# HABduino1_1.net
KiCad netlist of a schematic drawn in EAGLE
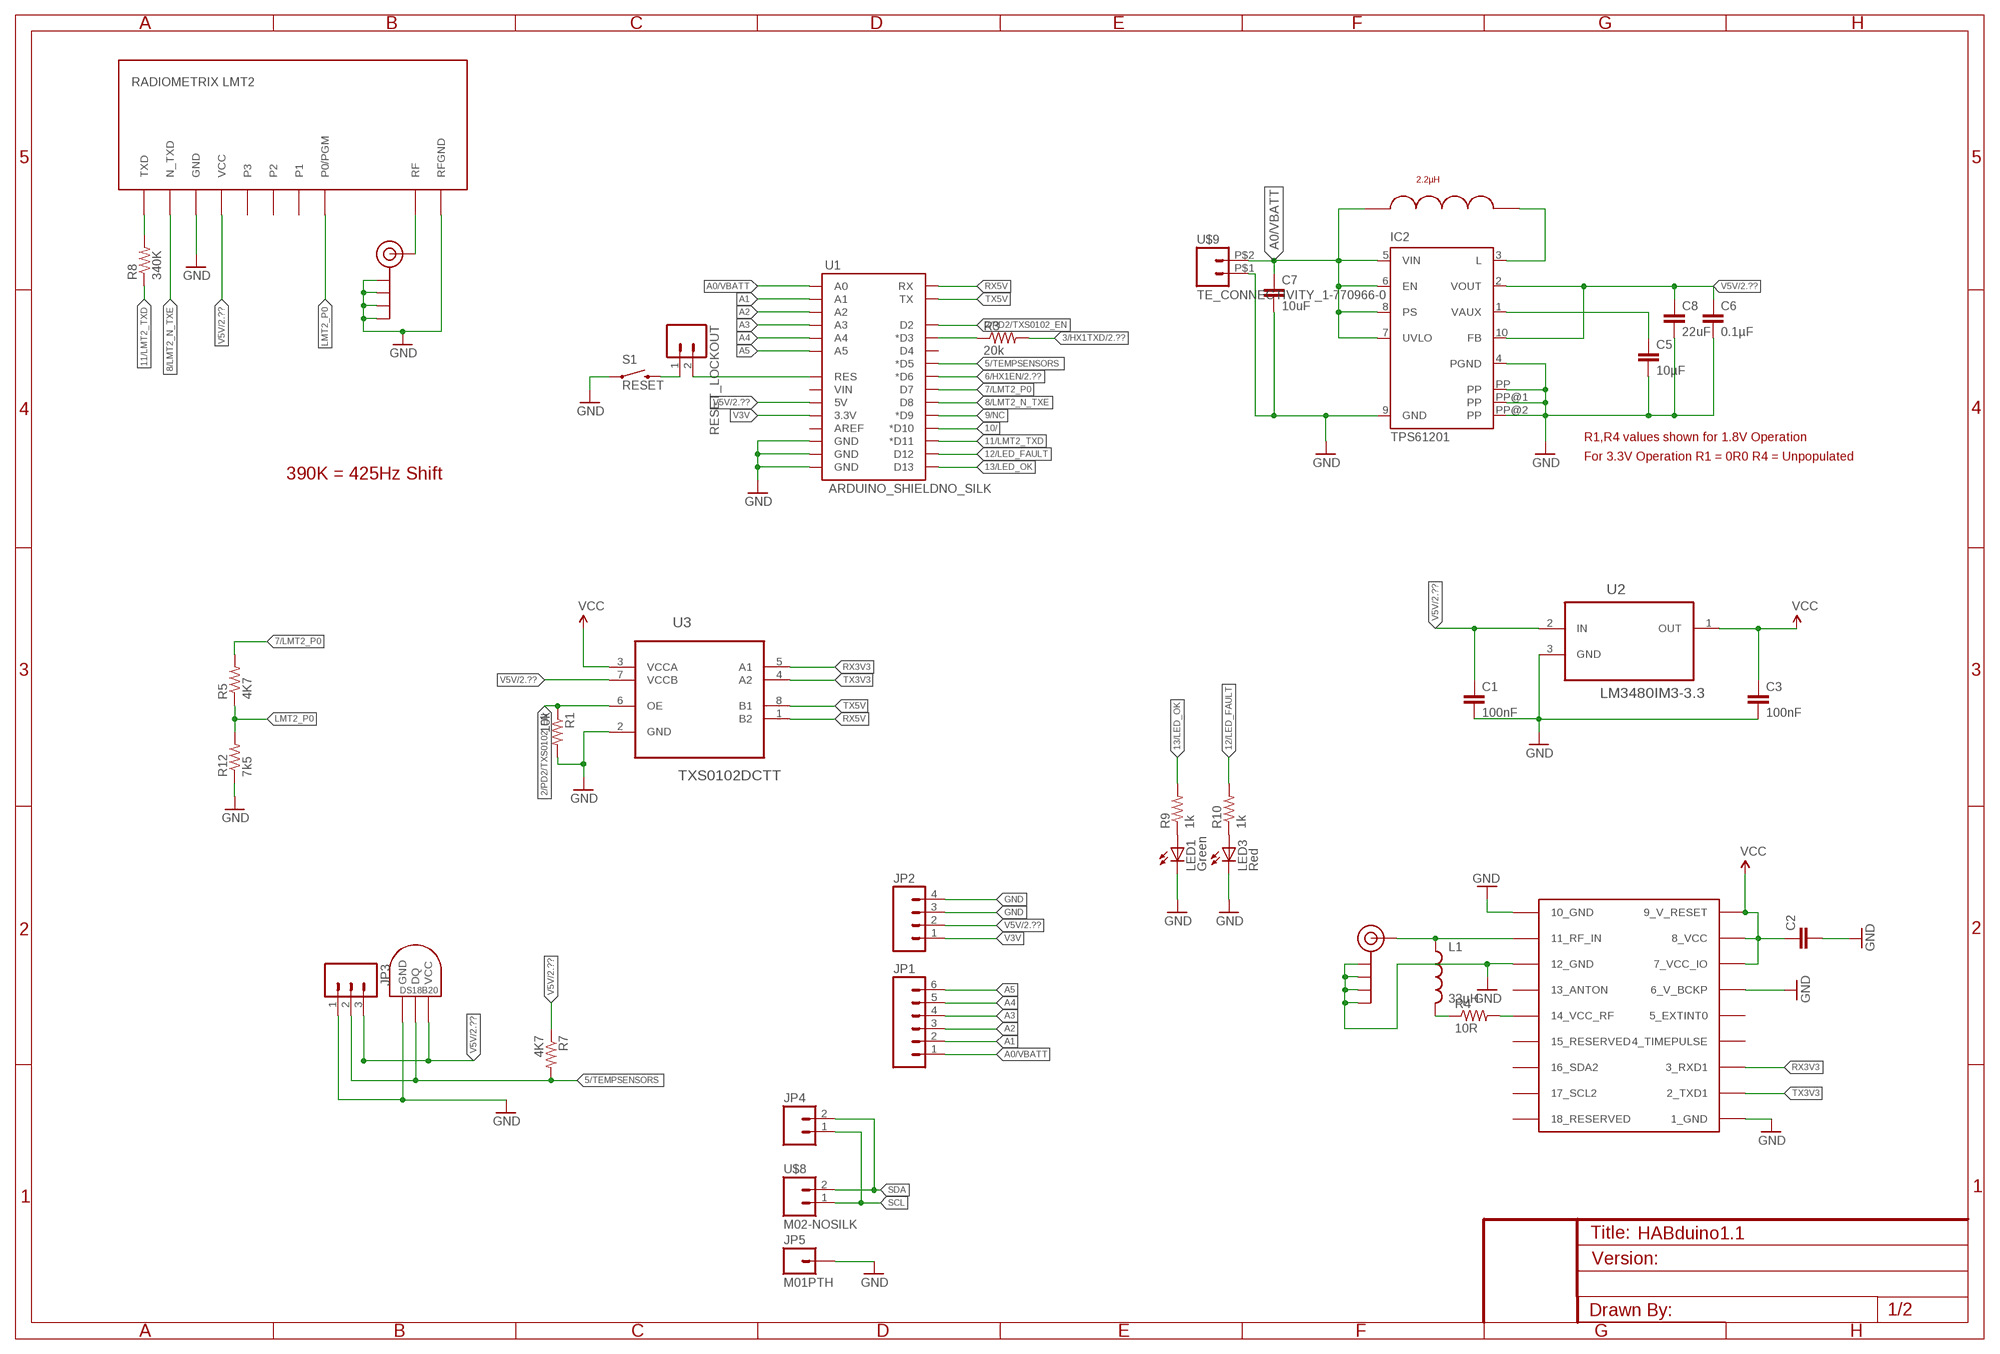
[diagram p0: schematic, sheet 1]
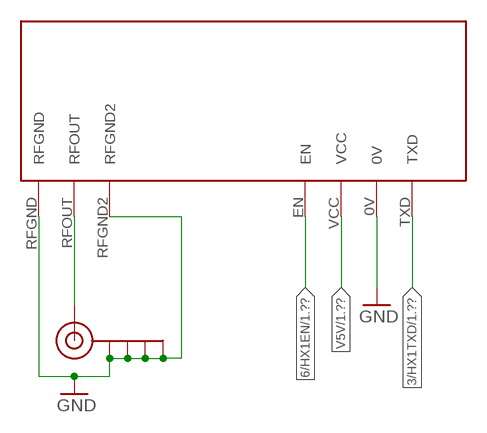
[diagram p1: schematic, sheet 2]

(export (version "E")
  (design (tool "Eeschema 10.0.6"))
  (components
    (comp (ref "C1")
      (value "100nF")
      (footprint "eagle-import:0603-CAP")
      (libsource (lib "eagle-import") (part "CAP0603-CAP"))
    )
    (comp (ref "C2")
      (value "CAP0603-CAP")
      (footprint "eagle-import:0603-CAP")
      (libsource (lib "eagle-import") (part "CAP0603-CAP"))
    )
    (comp (ref "C3")
      (value "100nF")
      (footprint "eagle-import:0603-CAP")
      (libsource (lib "eagle-import") (part "CAP0603-CAP"))
    )
    (comp (ref "C5")
      (value "10µF")
      (footprint "eagle-import:0603-CAP")
      (libsource (lib "eagle-import") (part "CAP0603-CAP"))
    )
    (comp (ref "C6")
      (value "0.1µF")
      (footprint "eagle-import:0603-CAP")
      (libsource (lib "eagle-import") (part "CAP0603-CAP"))
    )
    (comp (ref "C7")
      (value "10uF")
      (footprint "eagle-import:1206")
      (libsource (lib "eagle-import") (part "CAP1206"))
    )
    (comp (ref "C8")
      (value "22uF")
      (footprint "eagle-import:1206")
      (libsource (lib "eagle-import") (part "CAP1206"))
    )
    (comp (ref "IC2")
      (value "TPS61201")
      (footprint "eagle-import:S-PDSO-N10")
      (fields (field (name "MPN") "TPS61201DRCT"))
      (libsource (lib "eagle-import") (part "TPS61201"))
    )
    (comp (ref "J$1")
      (value "SMA_EDGE")
      (footprint "eagle-import:SMA-EDGE")
      (libsource (lib "eagle-import") (part "SMA_EDGE"))
    )
    (comp (ref "J$2")
      (value "SMA_EDGE")
      (footprint "eagle-import:SMA-EDGE")
      (libsource (lib "eagle-import") (part "SMA_EDGE"))
    )
    (comp (ref "JP1")
      (value "M06SIP")
      (footprint "eagle-import:1X06")
      (libsource (lib "eagle-import") (part "M06SIP"))
    )
    (comp (ref "JP2")
      (value "M04PTH")
      (footprint "eagle-import:1X04")
      (libsource (lib "eagle-import") (part "M04PTH"))
    )
    (comp (ref "JP3")
      (value "M03PTH")
      (footprint "eagle-import:1X03")
      (libsource (lib "eagle-import") (part "M03PTH"))
    )
    (comp (ref "JP4")
      (value "M02PTH")
      (footprint "eagle-import:1X02")
      (libsource (lib "eagle-import") (part "M02PTH"))
    )
    (comp (ref "JP5")
      (value "M01PTH")
      (footprint "eagle-import:1X01")
      (libsource (lib "eagle-import") (part "M01PTH"))
    )
    (comp (ref "L1")
      (value "33µH")
      (footprint "eagle-import:0603")
      (libsource (lib "eagle-import") (part "INDUCTOR0603"))
    )
    (comp (ref "LED1")
      (value "Green")
      (footprint "eagle-import:LED-0603")
      (libsource (lib "eagle-import") (part "LED0603"))
    )
    (comp (ref "LED3")
      (value "Red")
      (footprint "eagle-import:LED-0603")
      (libsource (lib "eagle-import") (part "LED0603"))
    )
    (comp (ref "R1")
      (value "10k")
      (footprint "eagle-import:0603-RES")
      (libsource (lib "eagle-import") (part "RESISTOR0603-RES"))
    )
    (comp (ref "R3")
      (value "20k")
      (footprint "eagle-import:0603-RES")
      (libsource (lib "eagle-import") (part "RESISTOR0603-RES"))
    )
    (comp (ref "R4")
      (value "10R")
      (footprint "eagle-import:0603-RES")
      (libsource (lib "eagle-import") (part "RESISTOR0603-RES"))
    )
    (comp (ref "R5")
      (value "4K7")
      (footprint "eagle-import:0603-RES")
      (libsource (lib "eagle-import") (part "RESISTOR0603-RES"))
    )
    (comp (ref "R7")
      (value "4K7")
      (footprint "eagle-import:0603-RES")
      (libsource (lib "eagle-import") (part "RESISTOR0603-RES"))
    )
    (comp (ref "R8")
      (value "340K")
      (footprint "eagle-import:0603-RES")
      (libsource (lib "eagle-import") (part "RESISTOR0603-RES"))
    )
    (comp (ref "R9")
      (value "1k")
      (footprint "eagle-import:0603-RES")
      (libsource (lib "eagle-import") (part "RESISTOR0603-RES"))
    )
    (comp (ref "R10")
      (value "1k")
      (footprint "eagle-import:0603-RES")
      (libsource (lib "eagle-import") (part "RESISTOR0603-RES"))
    )
    (comp (ref "R12")
      (value "7k5")
      (footprint "eagle-import:0603-RES")
      (libsource (lib "eagle-import") (part "RESISTOR0603-RES"))
    )
    (comp (ref "RESET_LOCKOUT")
      (value "M02PTH")
      (footprint "eagle-import:1X02")
      (libsource (lib "eagle-import") (part "M02PTH"))
    )
    (comp (ref "S1")
      (value "RESET")
      (footprint "eagle-import:TACTILE_SWITCH_TALL")
      (libsource (lib "eagle-import") (part "SWITCH-MOMENTARY-2"))
    )
    (comp (ref "TEMPINT")
      (value "DS1821")
      (footprint "eagle-import:DS1820")
      (libsource (lib "eagle-import") (part "DS1820TO92"))
    )
    (comp (ref "U$1")
      (value "UBLOX_MAX-6")
      (footprint "eagle-import:UBLOX_MAX-6")
      (libsource (lib "eagle-import") (part "UBLOX_MAX-6"))
    )
    (comp (ref "U$2")
      (value "RADIOMETRIX_LMT2")
      (footprint "eagle-import:RADIOMETRIX-LMT2")
      (libsource (lib "eagle-import") (part "RADIOMETRIX_LMT2"))
    )
    (comp (ref "U$8")
      (value "M02-NOSILK")
      (footprint "eagle-import:M02-NOSILK")
      (libsource (lib "eagle-import") (part "M02-NOSILK"))
    )
    (comp (ref "U$9")
      (value "TE_CONNECTIVITY_1-770966-0")
      (footprint "eagle-import:TE_CONNECTIVITY_1-770966-0")
      (libsource (lib "eagle-import") (part "TE_CONNECTIVITY_1-770966-0"))
    )
    (comp (ref "U$10")
      (value "2.2µH")
      (footprint "eagle-import:COILCRAFT_LPS4018")
      (libsource (lib "eagle-import") (part "COILCRAFT_LPS4018"))
    )
    (comp (ref "U1")
      (value "ARDUINO_SHIELDNO_SILK")
      (footprint "eagle-import:DUEMILANOVE_VIAS")
      (libsource (lib "eagle-import") (part "ARDUINO_SHIELDNO_SILK"))
    )
    (comp (ref "U2")
      (value "LM3480IM3-3.3")
      (footprint "eagle-import:SOT95P251X112-3N")
      (libsource (lib "eagle-import") (part "LM3480IM3-3.3"))
    )
    (comp (ref "U3")
      (value "TXS0102DCTT")
      (footprint "eagle-import:SOP65P400X130-8N")
      (libsource (lib "eagle-import") (part "TXS0102DCTT"))
    )
    (comp (ref "J$3")
      (value "SMA_EDGE")
      (footprint "eagle-import:SMA-EDGE")
      (libsource (lib "eagle-import") (part "SMA_EDGE"))
    )
    (comp (ref "U$7")
      (value "RADIOMETRIX-HX1")
      (footprint "eagle-import:RADIOMETRIX-HX1")
      (libsource (lib "eagle-import") (part "RADIOMETRIX-HX1"))
    )
  )
  (nets
    (net (code "1") (name "2{slash}PD2{slash}TXS0102_EN") (class "Default")
      (node (ref "R1") (pin "1") (pinfunction "1_1") (pintype "passive"))
      (node (ref "U1") (pin "D2") (pinfunction "D2_D2") (pintype "bidirectional"))
      (node (ref "U3") (pin "6") (pinfunction "OE_6") (pintype "input"))
    )
    (net (code "2") (name "3{slash}HX1TXD") (class "Default")
      (node (ref "R3") (pin "2") (pinfunction "2_2") (pintype "passive"))
      (node (ref "U$7") (pin "TXD") (pinfunction "TXD_TXD") (pintype "bidirectional"))
    )
    (net (code "3") (name "5{slash}TEMPSENSORS") (class "Default")
      (node (ref "JP3") (pin "2") (pinfunction "2_2") (pintype "passive"))
      (node (ref "R7") (pin "2") (pinfunction "2_2") (pintype "passive"))
      (node (ref "TEMPINT") (pin "DQ") (pinfunction "DQ_DQ") (pintype "bidirectional"))
      (node (ref "U1") (pin "D5") (pinfunction "*D5_D5") (pintype "bidirectional"))
    )
    (net (code "4") (name "6{slash}HX1EN") (class "Default")
      (node (ref "U$7") (pin "EN") (pinfunction "EN_EN") (pintype "bidirectional"))
      (node (ref "U1") (pin "D6") (pinfunction "*D6_D6") (pintype "bidirectional"))
    )
    (net (code "5") (name "7{slash}LMT2_P0") (class "Default")
      (node (ref "R5") (pin "2") (pinfunction "2_2") (pintype "passive"))
      (node (ref "U1") (pin "D7") (pinfunction "D7_D7") (pintype "bidirectional"))
    )
    (net (code "6") (name "8{slash}LMT2_N_TXE") (class "Default")
      (node (ref "U$2") (pin "N_TXE") (pinfunction "N_TXD_N_TXE") (pintype "bidirectional"))
      (node (ref "U1") (pin "D8") (pinfunction "D8_D8") (pintype "bidirectional"))
    )
    (net (code "7") (name "9{slash}NC") (class "Default")
      (node (ref "U1") (pin "D9") (pinfunction "*D9_D9") (pintype "bidirectional"))
    )
    (net (code "8") (name "10{slash}") (class "Default")
      (node (ref "U1") (pin "D10") (pinfunction "*D10_D10") (pintype "bidirectional"))
    )
    (net (code "9") (name "11{slash}LMT2_TXD") (class "Default")
      (node (ref "R8") (pin "1") (pinfunction "1_1") (pintype "passive"))
      (node (ref "U1") (pin "D11") (pinfunction "*D11_D11") (pintype "bidirectional"))
    )
    (net (code "10") (name "12{slash}LED_FAULT") (class "Default")
      (node (ref "R10") (pin "2") (pinfunction "2_2") (pintype "passive"))
      (node (ref "U1") (pin "D12") (pinfunction "D12_D12") (pintype "bidirectional"))
    )
    (net (code "11") (name "13{slash}LED_OK") (class "Default")
      (node (ref "R9") (pin "2") (pinfunction "2_2") (pintype "passive"))
      (node (ref "U1") (pin "D13") (pinfunction "D13_D13") (pintype "bidirectional"))
    )
    (net (code "12") (name "A0{slash}VBATT") (class "Default")
      (node (ref "C7") (pin "1") (pinfunction "1_1") (pintype "passive"))
      (node (ref "IC2") (pin "5") (pinfunction "VIN_5") (pintype "input"))
      (node (ref "IC2") (pin "6") (pinfunction "EN_6") (pintype "input"))
      (node (ref "IC2") (pin "7") (pinfunction "UVLO_7") (pintype "input"))
      (node (ref "IC2") (pin "8") (pinfunction "PS_8") (pintype "input"))
      (node (ref "JP1") (pin "1") (pinfunction "1_1") (pintype "passive"))
      (node (ref "U$10") (pin "P$1") (pinfunction "P$1_P$1") (pintype "bidirectional"))
      (node (ref "U$9") (pin "P$2") (pinfunction "2_P$2") (pintype "passive"))
      (node (ref "U1") (pin "A0") (pinfunction "A0_A0") (pintype "bidirectional"))
    )
    (net (code "13") (name "A1") (class "Default")
      (node (ref "JP1") (pin "2") (pinfunction "2_2") (pintype "passive"))
      (node (ref "U1") (pin "A1") (pinfunction "A1_A1") (pintype "bidirectional"))
    )
    (net (code "14") (name "A2") (class "Default")
      (node (ref "JP1") (pin "3") (pinfunction "3_3") (pintype "passive"))
      (node (ref "U1") (pin "A2") (pinfunction "A2_A2") (pintype "bidirectional"))
    )
    (net (code "15") (name "A3") (class "Default")
      (node (ref "JP1") (pin "4") (pinfunction "4_4") (pintype "passive"))
      (node (ref "U1") (pin "A3") (pinfunction "A3_A3") (pintype "bidirectional"))
    )
    (net (code "16") (name "A4") (class "Default")
      (node (ref "JP1") (pin "5") (pinfunction "5_5") (pintype "passive"))
      (node (ref "U1") (pin "A4") (pinfunction "A4_A4") (pintype "bidirectional"))
    )
    (net (code "17") (name "A5") (class "Default")
      (node (ref "JP1") (pin "6") (pinfunction "6_6") (pintype "passive"))
      (node (ref "U1") (pin "A5") (pinfunction "A5_A5") (pintype "bidirectional"))
    )
    (net (code "18") (name "GND") (class "Default")
      (node (ref "C1") (pin "2") (pinfunction "2_2") (pintype "passive"))
      (node (ref "C2") (pin "2") (pinfunction "2_2") (pintype "passive"))
      (node (ref "C3") (pin "2") (pinfunction "2_2") (pintype "passive"))
      (node (ref "C5") (pin "2") (pinfunction "2_2") (pintype "passive"))
      (node (ref "C6") (pin "2") (pinfunction "2_2") (pintype "passive"))
      (node (ref "C7") (pin "2") (pinfunction "2_2") (pintype "passive"))
      (node (ref "C8") (pin "2") (pinfunction "2_2") (pintype "passive"))
      (node (ref "IC2") (pin "4") (pinfunction "PGND_4") (pintype "power_in"))
      (node (ref "IC2") (pin "9") (pinfunction "GND_9") (pintype "power_in"))
      (node (ref "IC2") (pin "PP") (pinfunction "PP_PP") (pintype "power_in"))
      (node (ref "IC2") (pin "PP@1") (pinfunction "PP_PP@1") (pintype "power_in"))
      (node (ref "IC2") (pin "PP@2") (pinfunction "PP_PP@2") (pintype "power_in"))
      (node (ref "J$1") (pin "GND@0") (pinfunction "GND_GND@0") (pintype "bidirectional"))
      (node (ref "J$1") (pin "GND@1") (pinfunction "GND_GND@1") (pintype "bidirectional"))
      (node (ref "J$1") (pin "GND@2") (pinfunction "GND_GND@2") (pintype "bidirectional"))
      (node (ref "J$1") (pin "GND@3") (pinfunction "GND_GND@3") (pintype "bidirectional"))
      (node (ref "J$2") (pin "GND@0") (pinfunction "GND_GND@0") (pintype "bidirectional"))
      (node (ref "J$2") (pin "GND@1") (pinfunction "GND_GND@1") (pintype "bidirectional"))
      (node (ref "J$2") (pin "GND@2") (pinfunction "GND_GND@2") (pintype "bidirectional"))
      (node (ref "J$2") (pin "GND@3") (pinfunction "GND_GND@3") (pintype "bidirectional"))
      (node (ref "J$3") (pin "GND@0") (pinfunction "GND_GND@0") (pintype "bidirectional"))
      (node (ref "J$3") (pin "GND@1") (pinfunction "GND_GND@1") (pintype "bidirectional"))
      (node (ref "J$3") (pin "GND@2") (pinfunction "GND_GND@2") (pintype "bidirectional"))
      (node (ref "J$3") (pin "GND@3") (pinfunction "GND_GND@3") (pintype "bidirectional"))
      (node (ref "JP2") (pin "3") (pinfunction "3_3") (pintype "passive"))
      (node (ref "JP2") (pin "4") (pinfunction "4_4") (pintype "passive"))
      (node (ref "JP3") (pin "1") (pinfunction "1_1") (pintype "passive"))
      (node (ref "JP5") (pin "1") (pinfunction "1_1") (pintype "passive"))
      (node (ref "LED1") (pin "C") (pinfunction "C_C") (pintype "passive"))
      (node (ref "LED3") (pin "C") (pinfunction "C_C") (pintype "passive"))
      (node (ref "R1") (pin "2") (pinfunction "2_2") (pintype "passive"))
      (node (ref "R12") (pin "1") (pinfunction "1_1") (pintype "passive"))
      (node (ref "S1") (pin "A2") (pinfunction "1_A2") (pintype "passive"))
      (node (ref "TEMPINT") (pin "GND") (pinfunction "GND_GND") (pintype "power_in"))
      (node (ref "U$1") (pin "10_GND") (pinfunction "10_GND_10_GND") (pintype "bidirectional"))
      (node (ref "U$1") (pin "12_GND") (pinfunction "12_GND_12_GND") (pintype "bidirectional"))
      (node (ref "U$1") (pin "1_GND") (pinfunction "1_GND_1_GND") (pintype "bidirectional"))
      (node (ref "U$1") (pin "6_V_BCKP") (pinfunction "6_V_BCKP_6_V_BCKP") (pintype "bidirectional"))
      (node (ref "U$2") (pin "GND") (pinfunction "GND_GND") (pintype "power_in"))
      (node (ref "U$2") (pin "RFGND") (pinfunction "RFGND_RFGND") (pintype "bidirectional"))
      (node (ref "U$7") (pin "0V") (pinfunction "0V_0V") (pintype "bidirectional"))
      (node (ref "U$7") (pin "RFGND") (pinfunction "RFGND_RFGND") (pintype "bidirectional"))
      (node (ref "U$7") (pin "RFGND2") (pinfunction "RFGND2_RFGND2") (pintype "bidirectional"))
      (node (ref "U$9") (pin "P$1") (pinfunction "1_P$1") (pintype "passive"))
      (node (ref "U1") (pin "GND@0") (pinfunction "GND_GND@0") (pintype "bidirectional"))
      (node (ref "U1") (pin "GND@1") (pinfunction "GND_GND@1") (pintype "bidirectional"))
      (node (ref "U1") (pin "GND@2") (pinfunction "GND_GND@2") (pintype "bidirectional"))
      (node (ref "U2") (pin "3") (pinfunction "GND_3") (pintype "passive"))
      (node (ref "U3") (pin "2") (pinfunction "GND_2") (pintype "passive"))
    )
    (net (code "19") (name "LMT2_P0") (class "Default")
      (node (ref "R12") (pin "2") (pinfunction "2_2") (pintype "passive"))
      (node (ref "R5") (pin "1") (pinfunction "1_1") (pintype "passive"))
      (node (ref "U$2") (pin "P0/PGM") (pinfunction "P0/PGM_P0/PGM") (pintype "bidirectional"))
    )
    (net (code "20") (name "Net-(IC2-L)") (class "Default")
      (node (ref "IC2") (pin "3") (pinfunction "L_3") (pintype "input"))
      (node (ref "U$10") (pin "P$2") (pinfunction "P$2_P$2") (pintype "bidirectional"))
    )
    (net (code "21") (name "Net-(IC2-VAUX)") (class "Default")
      (node (ref "C5") (pin "1") (pinfunction "1_1") (pintype "passive"))
      (node (ref "IC2") (pin "1") (pinfunction "VAUX_1") (pintype "bidirectional"))
    )
    (net (code "22") (name "Net-(J$1-SIGNAL)") (class "Default")
      (node (ref "J$1") (pin "SIG") (pinfunction "SIGNAL_SIG") (pintype "bidirectional"))
      (node (ref "U$2") (pin "RF") (pinfunction "RF_RF") (pintype "bidirectional"))
    )
    (net (code "23") (name "Net-(J$2-SIGNAL)") (class "Default")
      (node (ref "J$2") (pin "SIG") (pinfunction "SIGNAL_SIG") (pintype "bidirectional"))
      (node (ref "L1") (pin "1") (pinfunction "1_1") (pintype "passive"))
      (node (ref "U$1") (pin "11_RF_IN") (pinfunction "11_RF_IN_11_RF_IN") (pintype "bidirectional"))
    )
    (net (code "24") (name "Net-(J$3-SIGNAL)") (class "Default")
      (node (ref "J$3") (pin "SIG") (pinfunction "SIGNAL_SIG") (pintype "bidirectional"))
      (node (ref "U$7") (pin "RFOUT") (pinfunction "RFOUT_RFOUT") (pintype "bidirectional"))
    )
    (net (code "25") (name "Net-(L1-Pad2)") (class "Default")
      (node (ref "L1") (pin "2") (pinfunction "2_2") (pintype "passive"))
      (node (ref "R4") (pin "1") (pinfunction "1_1") (pintype "passive"))
    )
    (net (code "26") (name "Net-(LED1-PadA)") (class "Default")
      (node (ref "LED1") (pin "A") (pinfunction "A_A") (pintype "passive"))
      (node (ref "R9") (pin "1") (pinfunction "1_1") (pintype "passive"))
    )
    (net (code "27") (name "Net-(LED3-PadA)") (class "Default")
      (node (ref "LED3") (pin "A") (pinfunction "A_A") (pintype "passive"))
      (node (ref "R10") (pin "1") (pinfunction "1_1") (pintype "passive"))
    )
    (net (code "28") (name "Net-(R4-Pad2)") (class "Default")
      (node (ref "R4") (pin "2") (pinfunction "2_2") (pintype "passive"))
      (node (ref "U$1") (pin "14_VCC_RF") (pinfunction "14_VCC_RF_14_VCC_RF") (pintype "bidirectional"))
    )
    (net (code "29") (name "Net-(R8-Pad2)") (class "Default")
      (node (ref "R8") (pin "2") (pinfunction "2_2") (pintype "passive"))
      (node (ref "U$2") (pin "TXD") (pinfunction "TXD_TXD") (pintype "bidirectional"))
    )
    (net (code "30") (name "Net-(RESET_LOCKOUT-Pad2)") (class "Default")
      (node (ref "RESET_LOCKOUT") (pin "2") (pinfunction "2_2") (pintype "passive"))
      (node (ref "U1") (pin "RES") (pinfunction "RES_RES") (pintype "bidirectional"))
    )
    (net (code "31") (name "Net-(S1-2)") (class "Default")
      (node (ref "RESET_LOCKOUT") (pin "1") (pinfunction "1_1") (pintype "passive"))
      (node (ref "S1") (pin "B2") (pinfunction "2_B2") (pintype "passive"))
    )
    (net (code "32") (name "Net-(U1-*D3)") (class "Default")
      (node (ref "R3") (pin "1") (pinfunction "1_1") (pintype "passive"))
      (node (ref "U1") (pin "D3") (pinfunction "*D3_D3") (pintype "bidirectional"))
    )
    (net (code "33") (name "RX3V3") (class "Default")
      (node (ref "U$1") (pin "3_RXD1") (pinfunction "3_RXD1_3_RXD1") (pintype "bidirectional"))
      (node (ref "U3") (pin "5") (pinfunction "A1_5") (pintype "bidirectional"))
    )
    (net (code "34") (name "RX5V") (class "Default")
      (node (ref "U1") (pin "RX") (pinfunction "RX_RX") (pintype "bidirectional"))
      (node (ref "U3") (pin "1") (pinfunction "B2_1") (pintype "bidirectional"))
    )
    (net (code "35") (name "SCL") (class "Default")
      (node (ref "JP4") (pin "1") (pinfunction "1_1") (pintype "passive"))
      (node (ref "U$8") (pin "1") (pinfunction "1_1") (pintype "passive"))
    )
    (net (code "36") (name "SDA") (class "Default")
      (node (ref "JP4") (pin "2") (pinfunction "2_2") (pintype "passive"))
      (node (ref "U$8") (pin "2") (pinfunction "2_2") (pintype "passive"))
    )
    (net (code "37") (name "TX3V3") (class "Default")
      (node (ref "U$1") (pin "2_TXD1") (pinfunction "2_TXD1_2_TXD1") (pintype "bidirectional"))
      (node (ref "U3") (pin "4") (pinfunction "A2_4") (pintype "bidirectional"))
    )
    (net (code "38") (name "TX5V") (class "Default")
      (node (ref "U1") (pin "TX") (pinfunction "TX_TX") (pintype "bidirectional"))
      (node (ref "U3") (pin "8") (pinfunction "B1_8") (pintype "bidirectional"))
    )
    (net (code "39") (name "V3V") (class "Default")
      (node (ref "JP2") (pin "1") (pinfunction "1_1") (pintype "passive"))
      (node (ref "U1") (pin "3.3V") (pinfunction "3.3V_3.3V") (pintype "bidirectional"))
    )
    (net (code "40") (name "V5V") (class "Default")
      (node (ref "C1") (pin "1") (pinfunction "1_1") (pintype "passive"))
      (node (ref "C6") (pin "1") (pinfunction "1_1") (pintype "passive"))
      (node (ref "C8") (pin "1") (pinfunction "1_1") (pintype "passive"))
      (node (ref "IC2") (pin "10") (pinfunction "FB_10") (pintype "input"))
      (node (ref "IC2") (pin "2") (pinfunction "VOUT_2") (pintype "passive"))
      (node (ref "JP2") (pin "2") (pinfunction "2_2") (pintype "passive"))
      (node (ref "JP3") (pin "3") (pinfunction "3_3") (pintype "passive"))
      (node (ref "R7") (pin "1") (pinfunction "1_1") (pintype "passive"))
      (node (ref "TEMPINT") (pin "VDD") (pinfunction "VCC_VDD") (pintype "power_in"))
      (node (ref "U$2") (pin "VCC") (pinfunction "VCC_VCC") (pintype "power_in"))
      (node (ref "U$7") (pin "VCC") (pinfunction "VCC_VCC") (pintype "bidirectional"))
      (node (ref "U1") (pin "5V") (pinfunction "5V_5V") (pintype "bidirectional"))
      (node (ref "U2") (pin "2") (pinfunction "IN_2") (pintype "power_in"))
      (node (ref "U3") (pin "7") (pinfunction "VCCB_7") (pintype "power_in"))
    )
    (net (code "41") (name "VCC") (class "Default")
      (node (ref "C2") (pin "1") (pinfunction "1_1") (pintype "passive"))
      (node (ref "C3") (pin "1") (pinfunction "1_1") (pintype "passive"))
      (node (ref "U$1") (pin "7_VCC_IO") (pinfunction "7_VCC_IO_7_VCC_IO") (pintype "bidirectional"))
      (node (ref "U$1") (pin "8_VCC") (pinfunction "8_VCC_8_VCC") (pintype "bidirectional"))
      (node (ref "U$1") (pin "9_V_RESET") (pinfunction "9_V_RESET_9_V_RESET") (pintype "bidirectional"))
      (node (ref "U2") (pin "1") (pinfunction "OUT_1") (pintype "output"))
      (node (ref "U3") (pin "3") (pinfunction "VCCA_3") (pintype "power_in"))
    )
    (net (code "42") (name "unconnected-(U$1-Pad4_TIMEPULSE)") (class "Default")
      (node (ref "U$1") (pin "4_TIMEPULSE") (pinfunction "4_TIMEPULSE_4_TIMEPULSE") (pintype "bidirectional"))
    )
    (net (code "43") (name "unconnected-(U$1-Pad5_EXTINT0)") (class "Default")
      (node (ref "U$1") (pin "5_EXTINT0") (pinfunction "5_EXTINT0_5_EXTINT0") (pintype "bidirectional"))
    )
    (net (code "44") (name "unconnected-(U$1-Pad13_ANTON)") (class "Default")
      (node (ref "U$1") (pin "13_ANTON") (pinfunction "13_ANTON_13_ANTON") (pintype "bidirectional"))
    )
    (net (code "45") (name "unconnected-(U$1-Pad15_RESERVED)") (class "Default")
      (node (ref "U$1") (pin "15_RESERVED") (pinfunction "15_RESERVED_15_RESERVED") (pintype "bidirectional"))
    )
    (net (code "46") (name "unconnected-(U$1-Pad16_SDA2)") (class "Default")
      (node (ref "U$1") (pin "16_SDA2") (pinfunction "16_SDA2_16_SDA2") (pintype "bidirectional"))
    )
    (net (code "47") (name "unconnected-(U$1-Pad17_SCL2)") (class "Default")
      (node (ref "U$1") (pin "17_SCL2") (pinfunction "17_SCL2_17_SCL2") (pintype "bidirectional"))
    )
    (net (code "48") (name "unconnected-(U$1-Pad18_RESERVED)") (class "Default")
      (node (ref "U$1") (pin "18_RESERVED") (pinfunction "18_RESERVED_18_RESERVED") (pintype "bidirectional"))
    )
    (net (code "49") (name "unconnected-(U$2-PadP1)") (class "Default")
      (node (ref "U$2") (pin "P1") (pinfunction "P1_P1") (pintype "bidirectional"))
    )
    (net (code "50") (name "unconnected-(U$2-PadP2)") (class "Default")
      (node (ref "U$2") (pin "P2") (pinfunction "P2_P2") (pintype "bidirectional"))
    )
    (net (code "51") (name "unconnected-(U$2-PadP3)") (class "Default")
      (node (ref "U$2") (pin "P3") (pinfunction "P3_P3") (pintype "bidirectional"))
    )
    (net (code "52") (name "unconnected-(U1-PadAREF)") (class "Default")
      (node (ref "U1") (pin "AREF") (pinfunction "AREF_AREF") (pintype "bidirectional"))
    )
    (net (code "53") (name "unconnected-(U1-PadD4)") (class "Default")
      (node (ref "U1") (pin "D4") (pinfunction "D4_D4") (pintype "bidirectional"))
    )
    (net (code "54") (name "unconnected-(U1-PadVIN)") (class "Default")
      (node (ref "U1") (pin "VIN") (pinfunction "VIN_VIN") (pintype "bidirectional"))
    )
  )
)
